# REGULACION.net
KiCad netlist of a schematic drawn in Altium Designer
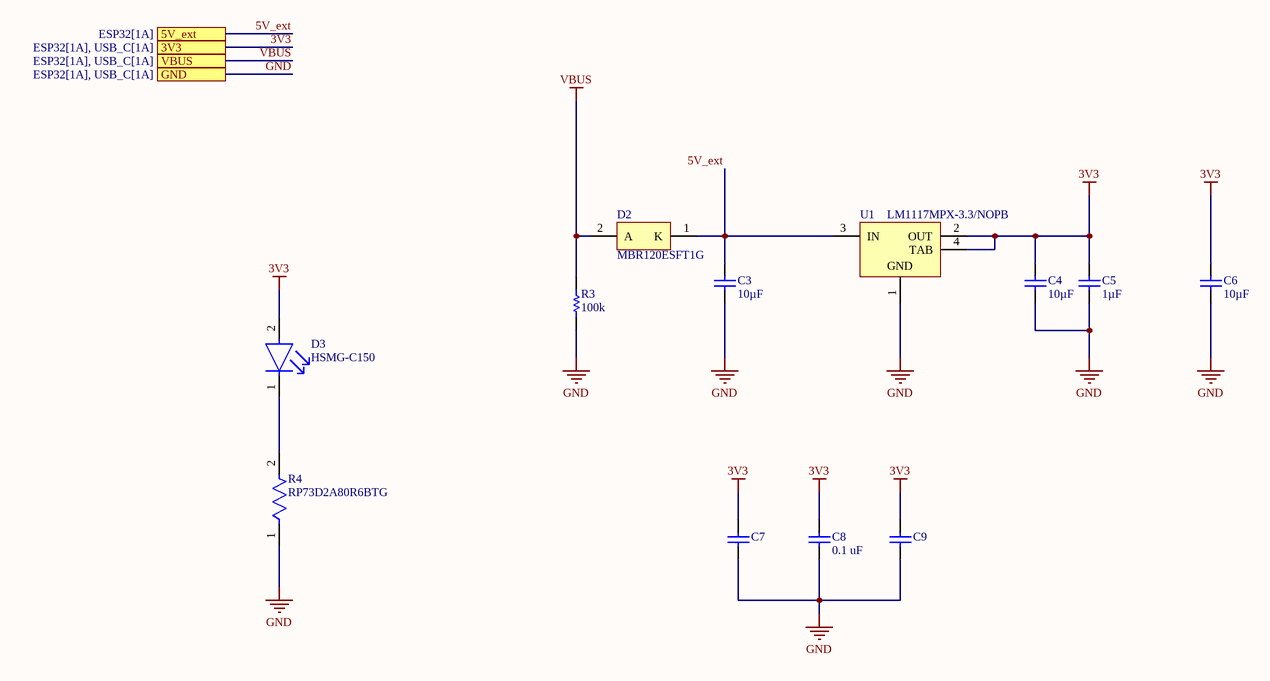
[diagram p0: REGULACION.SchDoc]

(export (version "E")
  (design (tool "Eeschema 10.0.6"))
  (components
    (comp (ref "C3")
      (value "10µF")
      (footprint "CAPC2013X140X50ML20T25")
      (description "10µF ±10% 16V Ceramic Capacitor X5R 0805 (2012 Metric)")
      (fields (field (name "PART NUMBER") "CL21A106KOQNNNG"))
      (libsource (lib "Altium Content Vault") (part "CAP"))
    )
    (comp (ref "C4")
      (value "10µF")
      (footprint "CAPC2013X140X50ML20T25")
      (description "10µF ±10% 16V Ceramic Capacitor X5R 0805 (2012 Metric)")
      (fields (field (name "PART NUMBER") "CL21A106KOQNNNG"))
      (libsource (lib "Altium Content Vault") (part "CAP"))
    )
    (comp (ref "C5")
      (value "1µF")
      (footprint "CAPC2013X145X50ML20T25")
      (description "1µF ±10% 16V Ceramic Capacitor X7R 0805 (2012 Metric)")
      (fields (field (name "MANUFACTURER") "Kemet") (field (name "PART NUMBER") "C0805C105K4RAC7800"))
      (libsource (lib "Altium Content Vault") (part "CAP"))
    )
    (comp (ref "C6")
      (value "10µF")
      (footprint "CAPC2013X140X50ML20T25")
      (description "10µF ±10% 16V Ceramic Capacitor X5R 0805 (2012 Metric)")
      (fields (field (name "PART NUMBER") "CL21A106KOQNNNG"))
      (libsource (lib "Altium Content Vault") (part "CAP"))
    )
    (comp (ref "C7")
      (value "C0805C106K4PACTU")
      (footprint "CAPC2013X140X50ML20T25")
      (description "10µF ±10% 16V Ceramic Capacitor X5R 0805 (2012 Metric)")
      (fields (field (name "PART NUMBER") "CL21A106KOQNNNG"))
      (libsource (lib "Altium Content Vault") (part "CAP"))
    )
    (comp (ref "C8")
      (value "0.1 uF")
      (footprint "CAPC2013X94X50ML20T25")
      (description "Chip Capacitor, Ceramic, 0.1 uF, 10%, 50 V, 0805, RoHS, Tape and Reel")
      (fields (field (name "MANUFACTURER") "AVX"))
      (libsource (lib "Altium Content Vault") (part "CAP-NP-2"))
    )
    (comp (ref "C9")
      (value "C0805C106K4PACTU")
      (footprint "CAPC2013X140X50ML20T25")
      (description "10µF ±10% 16V Ceramic Capacitor X5R 0805 (2012 Metric)")
      (fields (field (name "PART NUMBER") "CL21A106KOQNNNG"))
      (libsource (lib "Altium Content Vault") (part "CAP"))
    )
    (comp (ref "D2")
      (value "MBR120ESFT1G")
      (footprint "ONSC-SOD-123FL-2-498_V")
      (description "Schottky Power Rectifier, 2-Pin SOD-123, Pb-Free, Tape and Reel")
      (fields (field (name "MANUFACTURER") "On Semiconductor"))
      (libsource (lib "Altium Content Vault") (part "ONSC-D-K1A2-2_A"))
    )
    (comp (ref "D3")
      (value "HSMG-C150")
      (footprint "FP-HSMG-C150-MFG")
      (description "LED GREEN DIFFUSED 1206 SMD")
      (fields
        (field (name "MANUFACTURER") "Broadcom")
        (field (name "OCTOPART") "https://octopart.com/hsmg-c150-broadcom-71131304")
      )
      (libsource (lib "Altium Content Vault") (part "8706943c75ba83719d021d2fdc84c58"))
    )
    (comp (ref "R3")
      (value "100k")
      (footprint "RESC2013X60X40ML20T25")
      (description "100 kOhms ±0.1% 0.125W, 1/8W Chip Resistor 0805 (2012 Metric) Automotive AEC-Q200 Thin Film")
      (fields (field (name "PART NUMBER") "ERA6AEB104V") (field (name "MANUFACTURER") "Panasonic"))
      (libsource (lib "Altium Content Vault") (part "RES"))
    )
    (comp (ref "R4")
      (value "RP73D2A80R6BTG")
      (footprint "FP-RP732A-IPC_A")
      (description "RESISTOR, 0805 80.6Ω, 0.1% 15ppm/°C")
      (fields
        (field (name "OCTOPART") "https://octopart.com/rp73d2a80r6btg-te+connectivity-42011633")
        (field (name "MANUFACTURER") "TE Connectivity")
      )
      (libsource (lib "Altium Content Vault") (part "1029c3af85768c4190bb7ad29bc67b5"))
    )
    (comp (ref "U1")
      (value "LM1117MPX-3.3/NOPB")
      (footprint "DCY0004A_M")
      (description "800mA Low-Dropout Linear Regulator, 4-pin SOT-223, Pb-Free")
      (fields (field (name "MANUFACTURER") "Texas Instruments"))
      (libsource (lib "Altium Content Vault") (part "PM-REG-LM1086-SOT4"))
    )
  )
  (nets
    (net (code "1") (name "/5V_ext") (class "Default")
      (node (ref "C3") (pin "2") (pinfunction "2_2") (pintype "passive"))
      (node (ref "D2") (pin "1") (pinfunction "K_1") (pintype "passive"))
      (node (ref "U1") (pin "3") (pinfunction "IN_3") (pintype "power_in"))
    )
    (net (code "2") (name "3V3") (class "Default")
      (node (ref "C4") (pin "2") (pinfunction "2_2") (pintype "passive"))
      (node (ref "C5") (pin "2") (pinfunction "2_2") (pintype "passive"))
      (node (ref "C6") (pin "2") (pinfunction "2_2") (pintype "passive"))
      (node (ref "C7") (pin "2") (pinfunction "2_2") (pintype "passive"))
      (node (ref "C8") (pin "2") (pinfunction "2_2") (pintype "passive"))
      (node (ref "C9") (pin "2") (pinfunction "2_2") (pintype "passive"))
      (node (ref "D3") (pin "2") (pinfunction "A_2") (pintype "passive"))
      (node (ref "U1") (pin "2") (pinfunction "OUT_2") (pintype "power_in"))
      (node (ref "U1") (pin "4") (pinfunction "TAB_4") (pintype "power_in"))
    )
    (net (code "3") (name "GND") (class "Default")
      (node (ref "C3") (pin "1") (pinfunction "1_1") (pintype "passive"))
      (node (ref "C4") (pin "1") (pinfunction "1_1") (pintype "passive"))
      (node (ref "C5") (pin "1") (pinfunction "1_1") (pintype "passive"))
      (node (ref "C6") (pin "1") (pinfunction "1_1") (pintype "passive"))
      (node (ref "C7") (pin "1") (pinfunction "1_1") (pintype "passive"))
      (node (ref "C8") (pin "1") (pinfunction "1_1") (pintype "passive"))
      (node (ref "C9") (pin "1") (pinfunction "1_1") (pintype "passive"))
      (node (ref "R3") (pin "1") (pinfunction "1_1") (pintype "passive"))
      (node (ref "R4") (pin "1") (pinfunction "1_1") (pintype "passive"))
      (node (ref "U1") (pin "1") (pinfunction "GND_1") (pintype "power_in"))
    )
    (net (code "4") (name "Net-(D3-C)") (class "Default")
      (node (ref "D3") (pin "1") (pinfunction "C_1") (pintype "passive"))
      (node (ref "R4") (pin "2") (pinfunction "2_2") (pintype "passive"))
    )
    (net (code "5") (name "VBUS") (class "Default")
      (node (ref "D2") (pin "2") (pinfunction "A_2") (pintype "passive"))
      (node (ref "R3") (pin "2") (pinfunction "2_2") (pintype "passive"))
    )
  )
)
